# PDC.net
KiCad netlist of a schematic drawn in Altium Designer
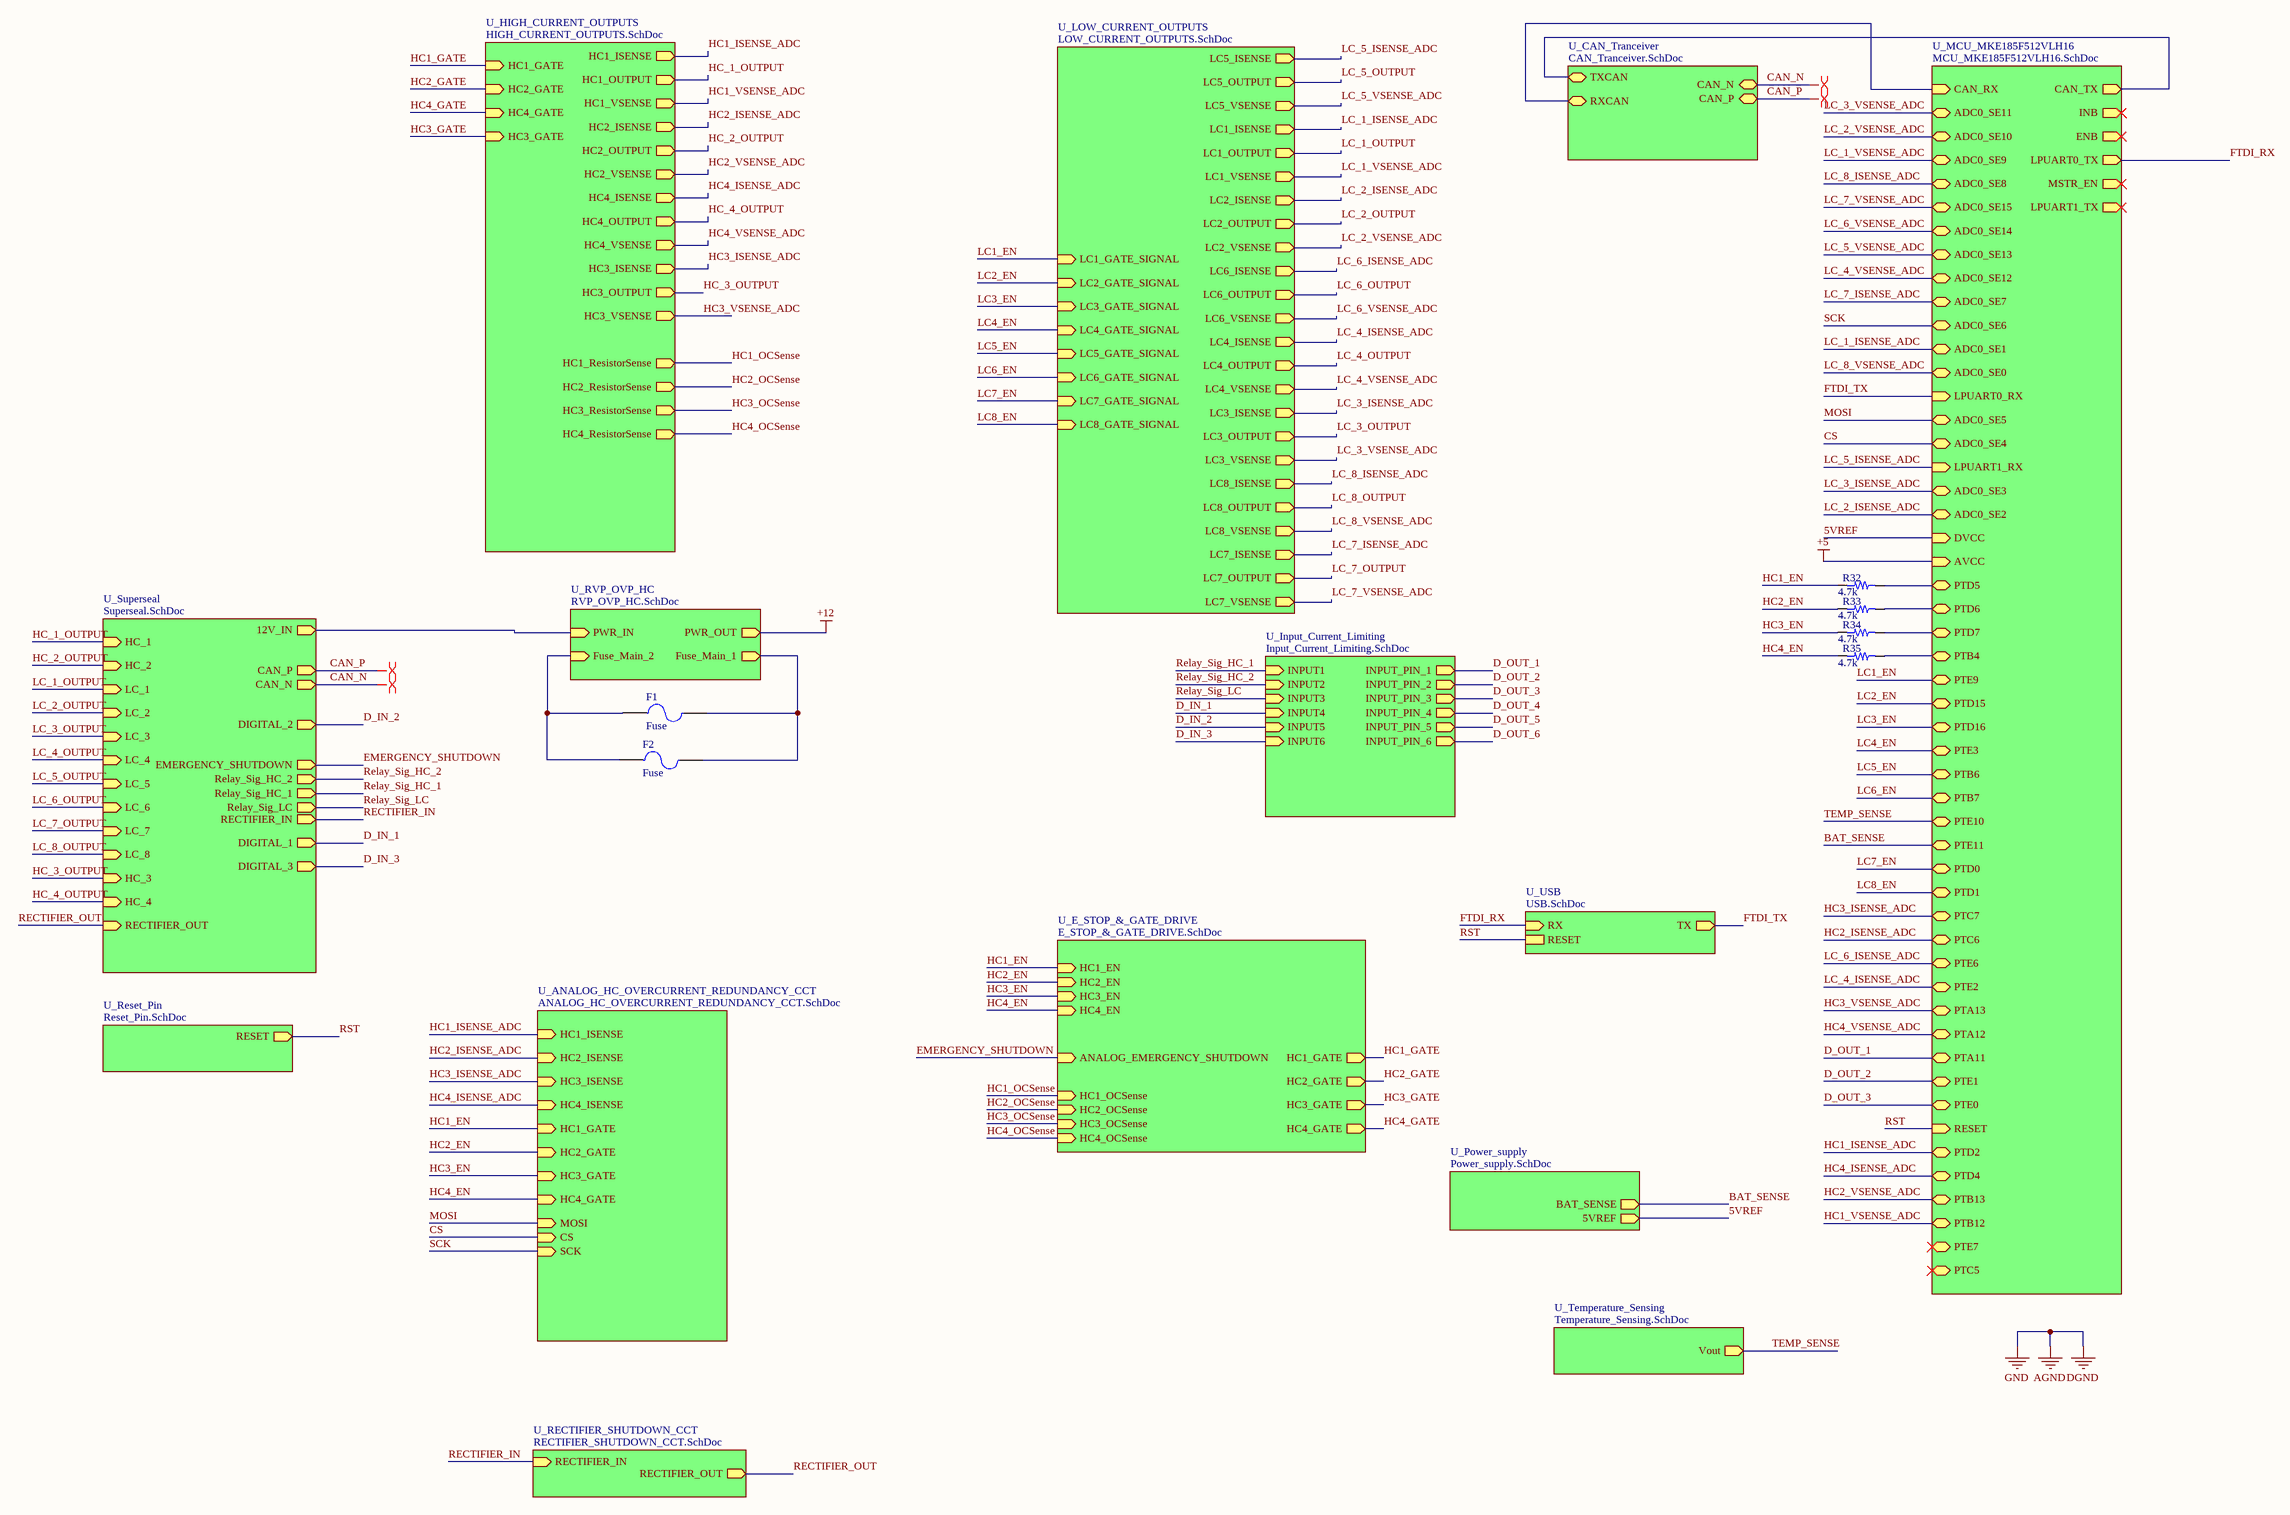
[diagram p0: PDC.SchDoc]

(export (version "E")
  (design (tool "Eeschema 10.0.6"))
  (components
    (comp (ref "F1")
      (value "Fuse")
      (footprint "3568-MiniFuseHolder")
      (libsource (lib "Altium-Lib") (part "Fuse"))
    )
    (comp (ref "F2")
      (value "Fuse")
      (footprint "3568-MiniFuseHolder")
      (libsource (lib "Altium-Lib") (part "Fuse"))
    )
    (comp (ref "R32")
      (value "4.7k")
      (footprint "RES 0603/1608")
      (fields (field (name "RESISTANCE") "4.7k"))
      (libsource (lib "altlib") (part "Resistor"))
    )
    (comp (ref "R33")
      (value "4.7k")
      (footprint "RES 0603/1608")
      (fields (field (name "RESISTANCE") "4.7k"))
      (libsource (lib "altlib") (part "Resistor"))
    )
    (comp (ref "R34")
      (value "4.7k")
      (footprint "RES 0603/1608")
      (fields (field (name "RESISTANCE") "4.7k"))
      (libsource (lib "altlib") (part "Resistor"))
    )
    (comp (ref "R35")
      (value "4.7k")
      (footprint "RES 0603/1608")
      (fields (field (name "RESISTANCE") "4.7k"))
      (libsource (lib "altlib") (part "Resistor"))
    )
  )
  (nets
    (net (code "24") (name "/Fuse_Main_1") (class "Default")
      (node (ref "F1") (pin "2") (pinfunction "2_2") (pintype "passive"))
      (node (ref "F2") (pin "2") (pinfunction "2_2") (pintype "passive"))
    )
    (net (code "25") (name "/Fuse_Main_2") (class "Default")
      (node (ref "F1") (pin "1") (pinfunction "1_1") (pintype "passive"))
      (node (ref "F2") (pin "1") (pinfunction "1_1") (pintype "passive"))
    )
    (net (code "26") (name "/HC1_EN") (class "Default")
      (node (ref "R32") (pin "1") (pinfunction "1_1") (pintype "passive"))
    )
    (net (code "31") (name "/HC2_EN") (class "Default")
      (node (ref "R33") (pin "1") (pinfunction "1_1") (pintype "passive"))
    )
    (net (code "36") (name "/HC3_EN") (class "Default")
      (node (ref "R34") (pin "1") (pinfunction "1_1") (pintype "passive"))
    )
    (net (code "41") (name "/HC4_EN") (class "Default")
      (node (ref "R35") (pin "1") (pinfunction "1_1") (pintype "passive"))
    )
    (net (code "86") (name "/PTB4") (class "Default")
      (node (ref "R35") (pin "2") (pinfunction "2_2") (pintype "passive"))
    )
    (net (code "88") (name "/PTD5") (class "Default")
      (node (ref "R32") (pin "2") (pinfunction "2_2") (pintype "passive"))
    )
    (net (code "89") (name "/PTD6") (class "Default")
      (node (ref "R33") (pin "2") (pinfunction "2_2") (pintype "passive"))
    )
    (net (code "90") (name "/PTD7") (class "Default")
      (node (ref "R34") (pin "2") (pinfunction "2_2") (pintype "passive"))
    )
  )
)
